# Clock.net
KiCad netlist of a schematic drawn in Altium Designer
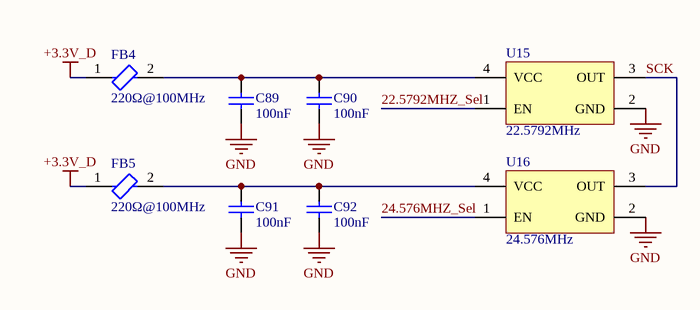
[diagram p0: Clock.SchDoc]

(export (version "E")
  (design (tool "Eeschema 10.0.6"))
  (components
    (comp (ref "C89")
      (value "100nF")
      (footprint "C 0402_L")
      (description "Capacitor")
      (fields (field (name "PUBLISHER") "Altium Limited"))
      (libsource (lib "Miscellaneous Devices") (part "Cap"))
    )
    (comp (ref "C90")
      (value "100nF")
      (footprint "C 0402_L")
      (description "Capacitor")
      (fields (field (name "PUBLISHER") "Altium Limited"))
      (libsource (lib "Miscellaneous Devices") (part "Cap"))
    )
    (comp (ref "C91")
      (value "100nF")
      (footprint "C 0402_L")
      (description "Capacitor")
      (fields (field (name "PUBLISHER") "Altium Limited"))
      (libsource (lib "Miscellaneous Devices") (part "Cap"))
    )
    (comp (ref "C92")
      (value "100nF")
      (footprint "C 0402_L")
      (description "Capacitor")
      (fields (field (name "PUBLISHER") "Altium Limited"))
      (libsource (lib "Miscellaneous Devices") (part "Cap"))
    )
    (comp (ref "FB4")
      (value "220Ω@100MHz")
      (footprint "FP-BLM18-0_15-t0_6-d1_2-MFG")
      (description "Chip Ferrite Bead Array, 0603, 100Ω @ 100MHz, 25%, 0.03Ω, 3A")
      (fields (field (name "TOLERANCE") "25%"))
      (libsource (lib "0603_FB") (part "CMP-0686-00548-4"))
    )
    (comp (ref "FB5")
      (value "220Ω@100MHz")
      (footprint "FP-BLM18-0_15-t0_6-d1_2-MFG")
      (description "Chip Ferrite Bead Array, 0603, 100Ω @ 100MHz, 25%, 0.03Ω, 3A")
      (fields (field (name "TOLERANCE") "25%"))
      (libsource (lib "0603_FB") (part "CMP-0686-00548-4"))
    )
    (comp (ref "U15")
      (value "22.5792MHz")
      (footprint "OSC 3225-4P")
      (libsource (lib "3225_Oscillator") (part "XTAL-ACT-4P"))
    )
    (comp (ref "U16")
      (value "24.576MHz")
      (footprint "OSC 3225-4P")
      (libsource (lib "3225_Oscillator") (part "XTAL-ACT-4P"))
    )
  )
  (nets
    (net (code "1") (name "+3.3V_D") (class "Default")
      (node (ref "FB4") (pin "1") (pinfunction "1_1") (pintype "passive"))
      (node (ref "FB5") (pin "1") (pinfunction "1_1") (pintype "passive"))
    )
    (net (code "2") (name "/22.5792MHZ_Sel") (class "Default")
      (node (ref "U15") (pin "1") (pinfunction "EN_1") (pintype "passive"))
    )
    (net (code "3") (name "/24.576MHZ_Sel") (class "Default")
      (node (ref "U16") (pin "1") (pinfunction "EN_1") (pintype "passive"))
    )
    (net (code "4") (name "/SCK") (class "Default")
      (node (ref "U15") (pin "3") (pinfunction "OUT_3") (pintype "passive"))
      (node (ref "U16") (pin "3") (pinfunction "OUT_3") (pintype "passive"))
    )
    (net (code "5") (name "GND") (class "Default")
      (node (ref "C89") (pin "2") (pinfunction "2_2") (pintype "passive"))
      (node (ref "C90") (pin "2") (pinfunction "2_2") (pintype "passive"))
      (node (ref "C91") (pin "2") (pinfunction "2_2") (pintype "passive"))
      (node (ref "C92") (pin "2") (pinfunction "2_2") (pintype "passive"))
      (node (ref "U15") (pin "2") (pinfunction "GND_2") (pintype "passive"))
      (node (ref "U16") (pin "2") (pinfunction "GND_2") (pintype "passive"))
    )
    (net (code "6") (name "Net-(U15-VCC)") (class "Default")
      (node (ref "C89") (pin "1") (pinfunction "1_1") (pintype "passive"))
      (node (ref "C90") (pin "1") (pinfunction "1_1") (pintype "passive"))
      (node (ref "FB4") (pin "2") (pinfunction "2_2") (pintype "passive"))
      (node (ref "U15") (pin "4") (pinfunction "VCC_4") (pintype "passive"))
    )
    (net (code "7") (name "Net-(U16-VCC)") (class "Default")
      (node (ref "C91") (pin "1") (pinfunction "1_1") (pintype "passive"))
      (node (ref "C92") (pin "1") (pinfunction "1_1") (pintype "passive"))
      (node (ref "FB5") (pin "2") (pinfunction "2_2") (pintype "passive"))
      (node (ref "U16") (pin "4") (pinfunction "VCC_4") (pintype "passive"))
    )
  )
)
